# core.net
KiCad netlist of a schematic drawn in Altium Designer
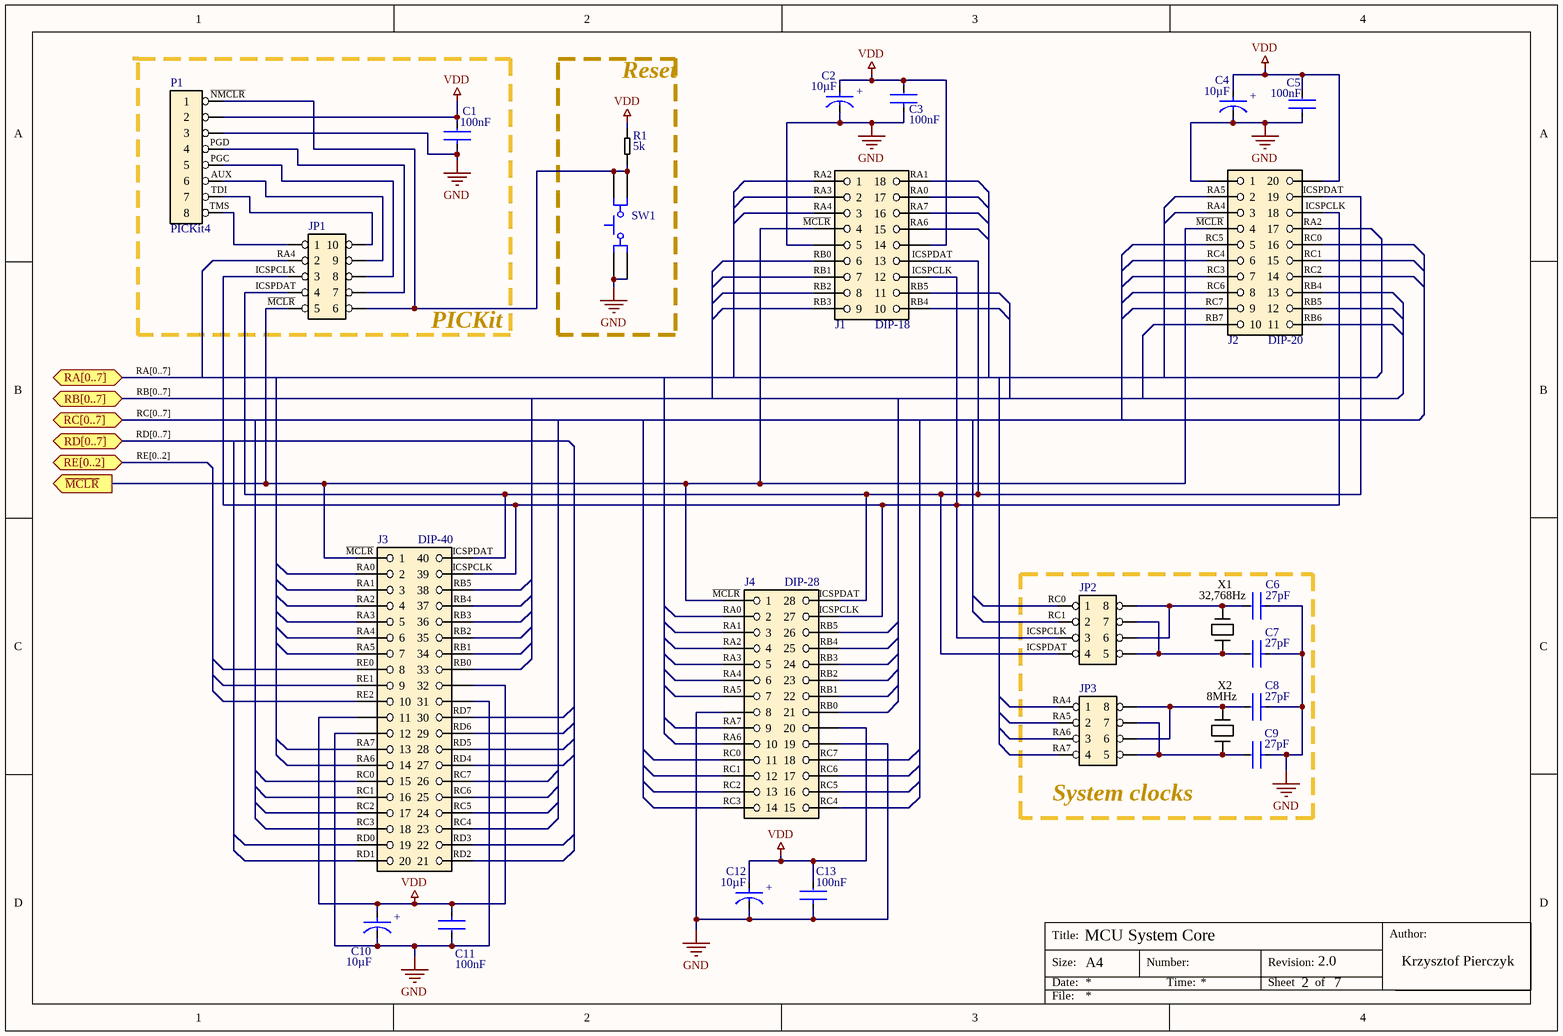
[diagram p0: core.SchDoc]

(export (version "E")
  (design (tool "Eeschema 10.0.6"))
  (components
    (comp (ref "C1")
      (value "100nF")
      (footprint "FP-C0805C-DN-MFG")
      (description "CAP CER 1000PF 50V C0G/NP0 0805")
      (fields
        (field (name "MANUFACTURER") "KEMET")
        (field (name "OCTOPART") "https://octopart.com/c0805c102j5gactu-kemet-97757")
      )
      (libsource (lib "Altium Content Vault") (part "b4654b650e69147ec39a6b967a45e02"))
    )
    (comp (ref "C2")
      (value "F981C106MSAAS1")
      (footprint "FP-F98S-MFG")
      (description "CAP TANT 10UF 20% 16V 0805")
      (fields
        (field (name "TOLERANCE") "20%")
        (field (name "CAPACITANCE") "10µF")
        (field (name "OCTOPART") "https://octopart.com/f981c106msaas1-avx-49645945")
      )
      (libsource (lib "Altium Content Vault") (part "cf48714ba7e38822c1575c7ec0b6d1f"))
    )
    (comp (ref "C3")
      (value "100nF")
      (footprint "FP-C0805C-DN-MFG")
      (description "CAP CER 1000PF 50V C0G/NP0 0805")
      (fields
        (field (name "MANUFACTURER") "KEMET")
        (field (name "OCTOPART") "https://octopart.com/c0805c102j5gactu-kemet-97757")
      )
      (libsource (lib "Altium Content Vault") (part "b4654b650e69147ec39a6b967a45e02"))
    )
    (comp (ref "C4")
      (value "F981C106MSAAS1")
      (footprint "FP-F98S-MFG")
      (description "CAP TANT 10UF 20% 16V 0805")
      (fields
        (field (name "TOLERANCE") "20%")
        (field (name "CAPACITANCE") "10µF")
        (field (name "OCTOPART") "https://octopart.com/f981c106msaas1-avx-49645945")
      )
      (libsource (lib "Altium Content Vault") (part "cf48714ba7e38822c1575c7ec0b6d1f"))
    )
    (comp (ref "C5")
      (value "100nF")
      (footprint "FP-C0805C-DN-MFG")
      (description "CAP CER 1000PF 50V C0G/NP0 0805")
      (fields
        (field (name "MANUFACTURER") "KEMET")
        (field (name "OCTOPART") "https://octopart.com/c0805c102j5gactu-kemet-97757")
      )
      (libsource (lib "Altium Content Vault") (part "b4654b650e69147ec39a6b967a45e02"))
    )
    (comp (ref "C6")
      (value "27pF")
      (footprint "FP-C0805C-DN-MFG")
      (description "CAP CER 1000PF 50V C0G/NP0 0805")
      (fields
        (field (name "MANUFACTURER") "KEMET")
        (field (name "OCTOPART") "https://octopart.com/c0805c102j5gactu-kemet-97757")
      )
      (libsource (lib "Altium Content Vault") (part "b4654b650e69147ec39a6b967a45e02"))
    )
    (comp (ref "C7")
      (value "27pF")
      (footprint "FP-C0805C-DN-MFG")
      (description "CAP CER 1000PF 50V C0G/NP0 0805")
      (fields
        (field (name "MANUFACTURER") "KEMET")
        (field (name "OCTOPART") "https://octopart.com/c0805c102j5gactu-kemet-97757")
      )
      (libsource (lib "Altium Content Vault") (part "b4654b650e69147ec39a6b967a45e02"))
    )
    (comp (ref "C8")
      (value "27pF")
      (footprint "FP-C0805C-DN-MFG")
      (description "CAP CER 1000PF 50V C0G/NP0 0805")
      (fields
        (field (name "MANUFACTURER") "KEMET")
        (field (name "OCTOPART") "https://octopart.com/c0805c102j5gactu-kemet-97757")
      )
      (libsource (lib "Altium Content Vault") (part "b4654b650e69147ec39a6b967a45e02"))
    )
    (comp (ref "C9")
      (value "27pF")
      (footprint "FP-C0805C-DN-MFG")
      (description "CAP CER 1000PF 50V C0G/NP0 0805")
      (fields
        (field (name "MANUFACTURER") "KEMET")
        (field (name "OCTOPART") "https://octopart.com/c0805c102j5gactu-kemet-97757")
      )
      (libsource (lib "Altium Content Vault") (part "b4654b650e69147ec39a6b967a45e02"))
    )
    (comp (ref "C10")
      (value "F981C106MSAAS1")
      (footprint "FP-F98S-MFG")
      (description "CAP TANT 10UF 20% 16V 0805")
      (fields
        (field (name "TOLERANCE") "20%")
        (field (name "CAPACITANCE") "10µF")
        (field (name "OCTOPART") "https://octopart.com/f981c106msaas1-avx-49645945")
      )
      (libsource (lib "Altium Content Vault") (part "cf48714ba7e38822c1575c7ec0b6d1f"))
    )
    (comp (ref "C11")
      (value "100nF")
      (footprint "FP-C0805C-DN-MFG")
      (description "CAP CER 1000PF 50V C0G/NP0 0805")
      (fields
        (field (name "MANUFACTURER") "KEMET")
        (field (name "OCTOPART") "https://octopart.com/c0805c102j5gactu-kemet-97757")
      )
      (libsource (lib "Altium Content Vault") (part "b4654b650e69147ec39a6b967a45e02"))
    )
    (comp (ref "C12")
      (value "F981C106MSAAS1")
      (footprint "FP-F98S-MFG")
      (description "CAP TANT 10UF 20% 16V 0805")
      (fields
        (field (name "TOLERANCE") "20%")
        (field (name "CAPACITANCE") "10µF")
        (field (name "OCTOPART") "https://octopart.com/f981c106msaas1-avx-49645945")
      )
      (libsource (lib "Altium Content Vault") (part "cf48714ba7e38822c1575c7ec0b6d1f"))
    )
    (comp (ref "C13")
      (value "100nF")
      (footprint "FP-C0805C-DN-MFG")
      (description "CAP CER 1000PF 50V C0G/NP0 0805")
      (fields
        (field (name "MANUFACTURER") "KEMET")
        (field (name "OCTOPART") "https://octopart.com/c0805c102j5gactu-kemet-97757")
      )
      (libsource (lib "Altium Content Vault") (part "b4654b650e69147ec39a6b967a45e02"))
    )
    (comp (ref "J1") (value "DIP-18") (footprint "DIP18") (libsource (lib "goldpin") (part "DIP-18")))
    (comp (ref "J2") (value "DIP-20") (footprint "DIP20") (libsource (lib "goldpin") (part "DIP-20")))
    (comp (ref "J3") (value "DIP-40") (footprint "DIP40") (libsource (lib "goldpin") (part "DIP-40")))
    (comp (ref "J4") (value "DIP-28") (footprint "DIP28") (libsource (lib "goldpin") (part "DIP-28")))
    (comp (ref "JP1")
      (value "Header 2x5")
      (footprint "Header2x5")
      (libsource (lib "goldpin") (part "Header 2x5"))
    )
    (comp (ref "JP2")
      (value "Header 2x4")
      (footprint "Header 2x4")
      (libsource (lib "goldpin") (part "Header 2x4"))
    )
    (comp (ref "JP3")
      (value "Header 2x4")
      (footprint "Header 2x4")
      (libsource (lib "goldpin") (part "Header 2x4"))
    )
    (comp (ref "P1")
      (value "PICKit4")
      (footprint "Header 1x8H")
      (libsource (lib "goldpin") (part "Header 1x8 A"))
    )
    (comp (ref "R1")
      (value "Resistor")
      (footprint "0805")
      (fields (field (name "RESISTANCE") "5k"))
      (libsource (lib "passive") (part "Resistor"))
    )
    (comp (ref "SW1")
      (value "4-1437565-1")
      (footprint "TECO-4-1437565-1_V")
      (description "Tactile Switch, 50 mA, 12 VDC, -20 to 85 degC, 4-Pin SMD, RoHS, Bulk")
      (fields (field (name "MANUFACTURER") "TEConnectivity/AMPBrand"))
      (libsource (lib "Altium Content Vault") (part "SW-SPST-NO-4"))
    )
    (comp (ref "X1")
      (value "Crystal")
      (footprint "X32K768S315")
      (fields (field (name "FREQUENCY") "32,768Hz"))
      (libsource (lib "miscellanea") (part "Crystal"))
    )
    (comp (ref "X2")
      (value "Crystal")
      (footprint "HC49SMP")
      (fields (field (name "FREQUENCY") "8MHz"))
      (libsource (lib "miscellanea") (part "Crystal"))
    )
  )
  (nets
    (net (code "1") (name "/AUX") (class "Default")
      (node (ref "JP1") (pin "9") (pinfunction "9_9") (pintype "passive"))
      (node (ref "P1") (pin "6") (pinfunction "6_6") (pintype "passive"))
    )
    (net (code "2") (name "/ICSPCLK") (class "Default")
      (node (ref "J1") (pin "12") (pinfunction "12_12") (pintype "passive"))
      (node (ref "J2") (pin "18") (pinfunction "18_18") (pintype "passive"))
      (node (ref "J3") (pin "39") (pinfunction "39_39") (pintype "passive"))
      (node (ref "J4") (pin "27") (pinfunction "27_27") (pintype "passive"))
      (node (ref "JP1") (pin "3") (pinfunction "3_3") (pintype "passive"))
      (node (ref "JP2") (pin "3") (pinfunction "3_3") (pintype "passive"))
    )
    (net (code "3") (name "/ICSPDAT") (class "Default")
      (node (ref "J1") (pin "13") (pinfunction "13_13") (pintype "passive"))
      (node (ref "J2") (pin "19") (pinfunction "19_19") (pintype "passive"))
      (node (ref "J3") (pin "40") (pinfunction "40_40") (pintype "passive"))
      (node (ref "J4") (pin "28") (pinfunction "28_28") (pintype "passive"))
      (node (ref "JP1") (pin "4") (pinfunction "4_4") (pintype "passive"))
      (node (ref "JP2") (pin "4") (pinfunction "4_4") (pintype "passive"))
    )
    (net (code "4") (name "/PGC") (class "Default")
      (node (ref "JP1") (pin "8") (pinfunction "8_8") (pintype "passive"))
      (node (ref "P1") (pin "5") (pinfunction "5_5") (pintype "passive"))
    )
    (net (code "5") (name "/PGD") (class "Default")
      (node (ref "JP1") (pin "7") (pinfunction "7_7") (pintype "passive"))
      (node (ref "P1") (pin "4") (pinfunction "4_4") (pintype "passive"))
    )
    (net (code "6") (name "/RA0") (class "Default")
      (node (ref "J1") (pin "17") (pinfunction "17_17") (pintype "passive"))
      (node (ref "J3") (pin "2") (pinfunction "2_2") (pintype "passive"))
      (node (ref "J4") (pin "2") (pinfunction "2_2") (pintype "passive"))
    )
    (net (code "7") (name "/RA1") (class "Default")
      (node (ref "J1") (pin "18") (pinfunction "18_18") (pintype "passive"))
      (node (ref "J3") (pin "3") (pinfunction "3_3") (pintype "passive"))
      (node (ref "J4") (pin "3") (pinfunction "3_3") (pintype "passive"))
    )
    (net (code "8") (name "/RA2") (class "Default")
      (node (ref "J1") (pin "1") (pinfunction "1_1") (pintype "passive"))
      (node (ref "J2") (pin "17") (pinfunction "17_17") (pintype "passive"))
      (node (ref "J3") (pin "4") (pinfunction "4_4") (pintype "passive"))
      (node (ref "J4") (pin "4") (pinfunction "4_4") (pintype "passive"))
    )
    (net (code "9") (name "/RA3") (class "Default")
      (node (ref "J1") (pin "2") (pinfunction "2_2") (pintype "passive"))
      (node (ref "J3") (pin "5") (pinfunction "5_5") (pintype "passive"))
      (node (ref "J4") (pin "5") (pinfunction "5_5") (pintype "passive"))
    )
    (net (code "10") (name "/RA4") (class "Default")
      (node (ref "J1") (pin "3") (pinfunction "3_3") (pintype "passive"))
      (node (ref "J2") (pin "3") (pinfunction "3_3") (pintype "passive"))
      (node (ref "J3") (pin "6") (pinfunction "6_6") (pintype "passive"))
      (node (ref "J4") (pin "6") (pinfunction "6_6") (pintype "passive"))
      (node (ref "JP1") (pin "2") (pinfunction "2_2") (pintype "passive"))
      (node (ref "JP3") (pin "1") (pinfunction "1_1") (pintype "passive"))
    )
    (net (code "11") (name "/RA5") (class "Default")
      (node (ref "J2") (pin "2") (pinfunction "2_2") (pintype "passive"))
      (node (ref "J3") (pin "7") (pinfunction "7_7") (pintype "passive"))
      (node (ref "J4") (pin "7") (pinfunction "7_7") (pintype "passive"))
      (node (ref "JP3") (pin "2") (pinfunction "2_2") (pintype "passive"))
    )
    (net (code "12") (name "/RA6") (class "Default")
      (node (ref "J1") (pin "15") (pinfunction "15_15") (pintype "passive"))
      (node (ref "J3") (pin "14") (pinfunction "14_14") (pintype "passive"))
      (node (ref "J4") (pin "10") (pinfunction "10_10") (pintype "passive"))
      (node (ref "JP3") (pin "3") (pinfunction "3_3") (pintype "passive"))
    )
    (net (code "13") (name "/RA7") (class "Default")
      (node (ref "J1") (pin "16") (pinfunction "16_16") (pintype "passive"))
      (node (ref "J3") (pin "13") (pinfunction "13_13") (pintype "passive"))
      (node (ref "J4") (pin "9") (pinfunction "9_9") (pintype "passive"))
      (node (ref "JP3") (pin "4") (pinfunction "4_4") (pintype "passive"))
    )
    (net (code "15") (name "/RB0") (class "Default")
      (node (ref "J1") (pin "6") (pinfunction "6_6") (pintype "passive"))
      (node (ref "J3") (pin "33") (pinfunction "33_33") (pintype "passive"))
      (node (ref "J4") (pin "21") (pinfunction "21_21") (pintype "passive"))
    )
    (net (code "16") (name "/RB1") (class "Default")
      (node (ref "J1") (pin "7") (pinfunction "7_7") (pintype "passive"))
      (node (ref "J3") (pin "34") (pinfunction "34_34") (pintype "passive"))
      (node (ref "J4") (pin "22") (pinfunction "22_22") (pintype "passive"))
    )
    (net (code "17") (name "/RB2") (class "Default")
      (node (ref "J1") (pin "8") (pinfunction "8_8") (pintype "passive"))
      (node (ref "J3") (pin "35") (pinfunction "35_35") (pintype "passive"))
      (node (ref "J4") (pin "23") (pinfunction "23_23") (pintype "passive"))
    )
    (net (code "18") (name "/RB3") (class "Default")
      (node (ref "J1") (pin "9") (pinfunction "9_9") (pintype "passive"))
      (node (ref "J3") (pin "36") (pinfunction "36_36") (pintype "passive"))
      (node (ref "J4") (pin "24") (pinfunction "24_24") (pintype "passive"))
    )
    (net (code "19") (name "/RB4") (class "Default")
      (node (ref "J1") (pin "10") (pinfunction "10_10") (pintype "passive"))
      (node (ref "J2") (pin "13") (pinfunction "13_13") (pintype "passive"))
      (node (ref "J3") (pin "37") (pinfunction "37_37") (pintype "passive"))
      (node (ref "J4") (pin "25") (pinfunction "25_25") (pintype "passive"))
    )
    (net (code "20") (name "/RB5") (class "Default")
      (node (ref "J1") (pin "11") (pinfunction "11_11") (pintype "passive"))
      (node (ref "J2") (pin "12") (pinfunction "12_12") (pintype "passive"))
      (node (ref "J3") (pin "38") (pinfunction "38_38") (pintype "passive"))
      (node (ref "J4") (pin "26") (pinfunction "26_26") (pintype "passive"))
    )
    (net (code "21") (name "/RB6") (class "Default")
      (node (ref "J2") (pin "11") (pinfunction "11_11") (pintype "passive"))
    )
    (net (code "22") (name "/RB7") (class "Default")
      (node (ref "J2") (pin "10") (pinfunction "10_10") (pintype "passive"))
    )
    (net (code "24") (name "/RC0") (class "Default")
      (node (ref "J2") (pin "16") (pinfunction "16_16") (pintype "passive"))
      (node (ref "J3") (pin "15") (pinfunction "15_15") (pintype "passive"))
      (node (ref "J4") (pin "11") (pinfunction "11_11") (pintype "passive"))
      (node (ref "JP2") (pin "1") (pinfunction "1_1") (pintype "passive"))
    )
    (net (code "25") (name "/RC1") (class "Default")
      (node (ref "J2") (pin "15") (pinfunction "15_15") (pintype "passive"))
      (node (ref "J3") (pin "16") (pinfunction "16_16") (pintype "passive"))
      (node (ref "J4") (pin "12") (pinfunction "12_12") (pintype "passive"))
      (node (ref "JP2") (pin "2") (pinfunction "2_2") (pintype "passive"))
    )
    (net (code "26") (name "/RC2") (class "Default")
      (node (ref "J2") (pin "14") (pinfunction "14_14") (pintype "passive"))
      (node (ref "J3") (pin "17") (pinfunction "17_17") (pintype "passive"))
      (node (ref "J4") (pin "13") (pinfunction "13_13") (pintype "passive"))
    )
    (net (code "27") (name "/RC3") (class "Default")
      (node (ref "J2") (pin "7") (pinfunction "7_7") (pintype "passive"))
      (node (ref "J3") (pin "18") (pinfunction "18_18") (pintype "passive"))
      (node (ref "J4") (pin "14") (pinfunction "14_14") (pintype "passive"))
    )
    (net (code "28") (name "/RC4") (class "Default")
      (node (ref "J2") (pin "6") (pinfunction "6_6") (pintype "passive"))
      (node (ref "J3") (pin "23") (pinfunction "23_23") (pintype "passive"))
      (node (ref "J4") (pin "15") (pinfunction "15_15") (pintype "passive"))
    )
    (net (code "29") (name "/RC5") (class "Default")
      (node (ref "J2") (pin "5") (pinfunction "5_5") (pintype "passive"))
      (node (ref "J3") (pin "24") (pinfunction "24_24") (pintype "passive"))
      (node (ref "J4") (pin "16") (pinfunction "16_16") (pintype "passive"))
    )
    (net (code "30") (name "/RC6") (class "Default")
      (node (ref "J2") (pin "8") (pinfunction "8_8") (pintype "passive"))
      (node (ref "J3") (pin "25") (pinfunction "25_25") (pintype "passive"))
      (node (ref "J4") (pin "17") (pinfunction "17_17") (pintype "passive"))
    )
    (net (code "31") (name "/RC7") (class "Default")
      (node (ref "J2") (pin "9") (pinfunction "9_9") (pintype "passive"))
      (node (ref "J3") (pin "26") (pinfunction "26_26") (pintype "passive"))
      (node (ref "J4") (pin "18") (pinfunction "18_18") (pintype "passive"))
    )
    (net (code "33") (name "/RD0") (class "Default")
      (node (ref "J3") (pin "19") (pinfunction "19_19") (pintype "passive"))
    )
    (net (code "34") (name "/RD1") (class "Default")
      (node (ref "J3") (pin "20") (pinfunction "20_20") (pintype "passive"))
    )
    (net (code "35") (name "/RD2") (class "Default")
      (node (ref "J3") (pin "21") (pinfunction "21_21") (pintype "passive"))
    )
    (net (code "36") (name "/RD3") (class "Default")
      (node (ref "J3") (pin "22") (pinfunction "22_22") (pintype "passive"))
    )
    (net (code "37") (name "/RD4") (class "Default")
      (node (ref "J3") (pin "27") (pinfunction "27_27") (pintype "passive"))
    )
    (net (code "38") (name "/RD5") (class "Default")
      (node (ref "J3") (pin "28") (pinfunction "28_28") (pintype "passive"))
    )
    (net (code "39") (name "/RD6") (class "Default")
      (node (ref "J3") (pin "29") (pinfunction "29_29") (pintype "passive"))
    )
    (net (code "40") (name "/RD7") (class "Default")
      (node (ref "J3") (pin "30") (pinfunction "30_30") (pintype "passive"))
    )
    (net (code "42") (name "/RE0") (class "Default")
      (node (ref "J3") (pin "8") (pinfunction "8_8") (pintype "passive"))
    )
    (net (code "43") (name "/RE1") (class "Default")
      (node (ref "J3") (pin "9") (pinfunction "9_9") (pintype "passive"))
    )
    (net (code "44") (name "/RE2") (class "Default")
      (node (ref "J3") (pin "10") (pinfunction "10_10") (pintype "passive"))
    )
    (net (code "46") (name "/TDI") (class "Default")
      (node (ref "JP1") (pin "10") (pinfunction "10_10") (pintype "passive"))
      (node (ref "P1") (pin "7") (pinfunction "7_7") (pintype "passive"))
    )
    (net (code "47") (name "/TMS") (class "Default")
      (node (ref "JP1") (pin "1") (pinfunction "1_1") (pintype "passive"))
      (node (ref "P1") (pin "8") (pinfunction "8_8") (pintype "passive"))
    )
    (net (code "48") (name "/~{MCLR}") (class "Default")
      (node (ref "J1") (pin "4") (pinfunction "4_4") (pintype "passive"))
      (node (ref "J2") (pin "4") (pinfunction "4_4") (pintype "passive"))
      (node (ref "J3") (pin "1") (pinfunction "1_1") (pintype "passive"))
      (node (ref "J4") (pin "1") (pinfunction "1_1") (pintype "passive"))
      (node (ref "JP1") (pin "5") (pinfunction "5_5") (pintype "passive"))
    )
    (net (code "49") (name "/~{NMCLR}") (class "Default")
      (node (ref "JP1") (pin "6") (pinfunction "6_6") (pintype "passive"))
      (node (ref "P1") (pin "1") (pinfunction "1_1") (pintype "passive"))
      (node (ref "R1") (pin "2") (pinfunction "2_2") (pintype "passive"))
      (node (ref "SW1") (pin "3") (pinfunction "3_3") (pintype "passive"))
      (node (ref "SW1") (pin "4") (pinfunction "4_4") (pintype "passive"))
    )
    (net (code "50") (name "GND") (class "Default")
      (node (ref "C1") (pin "1") (pinfunction "1_1") (pintype "passive"))
      (node (ref "C10") (pin "1") (pinfunction "C_1") (pintype "passive"))
      (node (ref "C11") (pin "2") (pinfunction "2_2") (pintype "passive"))
      (node (ref "C12") (pin "1") (pinfunction "C_1") (pintype "passive"))
      (node (ref "C13") (pin "1") (pinfunction "1_1") (pintype "passive"))
      (node (ref "C2") (pin "1") (pinfunction "C_1") (pintype "passive"))
      (node (ref "C3") (pin "1") (pinfunction "1_1") (pintype "passive"))
      (node (ref "C4") (pin "1") (pinfunction "C_1") (pintype "passive"))
      (node (ref "C5") (pin "1") (pinfunction "1_1") (pintype "passive"))
      (node (ref "C6") (pin "1") (pinfunction "1_1") (pintype "passive"))
      (node (ref "C7") (pin "1") (pinfunction "1_1") (pintype "passive"))
      (node (ref "C8") (pin "1") (pinfunction "1_1") (pintype "passive"))
      (node (ref "C9") (pin "1") (pinfunction "1_1") (pintype "passive"))
      (node (ref "J1") (pin "5") (pinfunction "5_5") (pintype "passive"))
      (node (ref "J2") (pin "1") (pinfunction "1_1") (pintype "passive"))
      (node (ref "J3") (pin "12") (pinfunction "12_12") (pintype "passive"))
      (node (ref "J3") (pin "31") (pinfunction "31_31") (pintype "passive"))
      (node (ref "J4") (pin "19") (pinfunction "19_19") (pintype "passive"))
      (node (ref "J4") (pin "8") (pinfunction "8_8") (pintype "passive"))
      (node (ref "P1") (pin "3") (pinfunction "3_3") (pintype "passive"))
      (node (ref "SW1") (pin "1") (pinfunction "1_1") (pintype "passive"))
      (node (ref "SW1") (pin "2") (pinfunction "2_2") (pintype "passive"))
    )
    (net (code "51") (name "Net-(C6-Pad2)") (class "Default")
      (node (ref "C6") (pin "2") (pinfunction "2_2") (pintype "passive"))
      (node (ref "JP2") (pin "6") (pinfunction "6_6") (pintype "passive"))
      (node (ref "JP2") (pin "8") (pinfunction "8_8") (pintype "passive"))
      (node (ref "X1") (pin "1") (pinfunction "1_1") (pintype "passive"))
    )
    (net (code "52") (name "Net-(C7-Pad2)") (class "Default")
      (node (ref "C7") (pin "2") (pinfunction "2_2") (pintype "passive"))
      (node (ref "JP2") (pin "5") (pinfunction "5_5") (pintype "passive"))
      (node (ref "JP2") (pin "7") (pinfunction "7_7") (pintype "passive"))
      (node (ref "X1") (pin "2") (pinfunction "2_2") (pintype "passive"))
    )
    (net (code "53") (name "Net-(C8-Pad2)") (class "Default")
      (node (ref "C8") (pin "2") (pinfunction "2_2") (pintype "passive"))
      (node (ref "JP3") (pin "6") (pinfunction "6_6") (pintype "passive"))
      (node (ref "JP3") (pin "8") (pinfunction "8_8") (pintype "passive"))
      (node (ref "X2") (pin "1") (pinfunction "1_1") (pintype "passive"))
    )
    (net (code "54") (name "Net-(C9-Pad2)") (class "Default")
      (node (ref "C9") (pin "2") (pinfunction "2_2") (pintype "passive"))
      (node (ref "JP3") (pin "5") (pinfunction "5_5") (pintype "passive"))
      (node (ref "JP3") (pin "7") (pinfunction "7_7") (pintype "passive"))
      (node (ref "X2") (pin "2") (pinfunction "2_2") (pintype "passive"))
    )
    (net (code "55") (name "VDD") (class "Default")
      (node (ref "C1") (pin "2") (pinfunction "2_2") (pintype "passive"))
      (node (ref "C10") (pin "2") (pinfunction "A_2") (pintype "passive"))
      (node (ref "C11") (pin "1") (pinfunction "1_1") (pintype "passive"))
      (node (ref "C12") (pin "2") (pinfunction "A_2") (pintype "passive"))
      (node (ref "C13") (pin "2") (pinfunction "2_2") (pintype "passive"))
      (node (ref "C2") (pin "2") (pinfunction "A_2") (pintype "passive"))
      (node (ref "C3") (pin "2") (pinfunction "2_2") (pintype "passive"))
      (node (ref "C4") (pin "2") (pinfunction "A_2") (pintype "passive"))
      (node (ref "C5") (pin "2") (pinfunction "2_2") (pintype "passive"))
      (node (ref "J1") (pin "14") (pinfunction "14_14") (pintype "passive"))
      (node (ref "J2") (pin "20") (pinfunction "20_20") (pintype "passive"))
      (node (ref "J3") (pin "11") (pinfunction "11_11") (pintype "passive"))
      (node (ref "J3") (pin "32") (pinfunction "32_32") (pintype "passive"))
      (node (ref "J4") (pin "20") (pinfunction "20_20") (pintype "passive"))
      (node (ref "P1") (pin "2") (pinfunction "2_2") (pintype "passive"))
      (node (ref "R1") (pin "1") (pinfunction "1_1") (pintype "passive"))
    )
  )
)
